# TSOC-ESP8266-EM-1-0.net
KiCad netlist of a schematic drawn in EAGLE
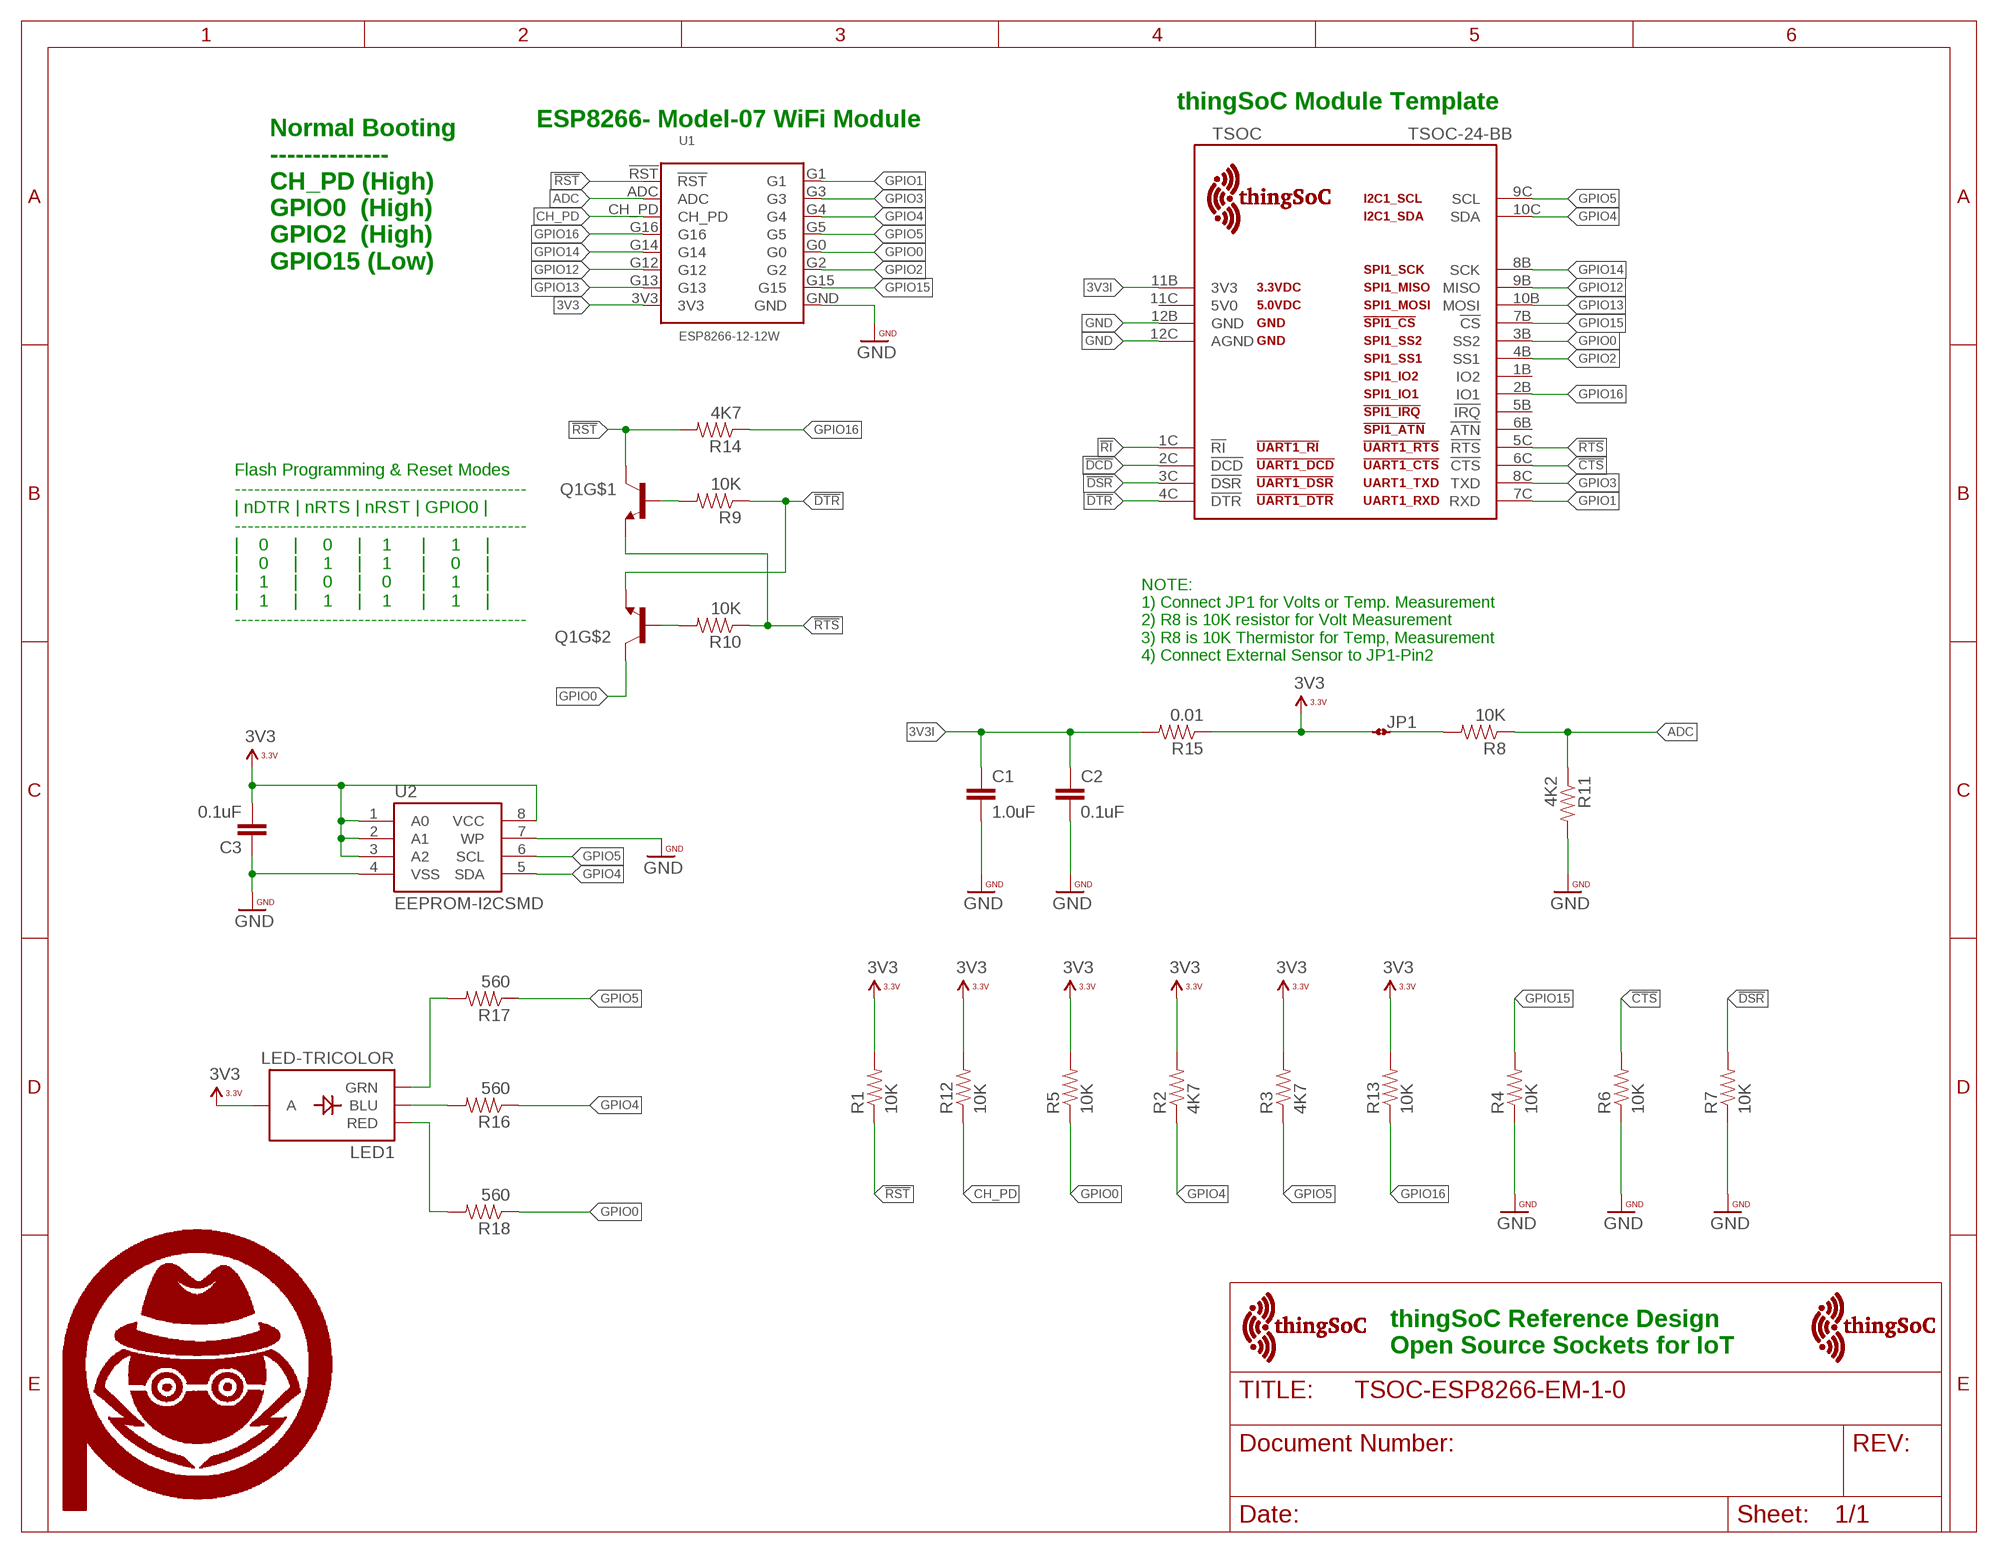
[diagram p0: schematic, sheet 1]

(export (version "E")
  (design (tool "Eeschema 10.0.6"))
  (components
    (comp (ref "C1")
      (value "1.0uF")
      (footprint "eagle-import:0402-CAP")
      (libsource (lib "eagle-import") (part "CAP0402-CAP"))
    )
    (comp (ref "C2")
      (value "0.1uF")
      (footprint "eagle-import:0402-CAP")
      (libsource (lib "eagle-import") (part "CAP0402-CAP"))
    )
    (comp (ref "C3")
      (value "0.1uF")
      (footprint "eagle-import:0402-CAP")
      (libsource (lib "eagle-import") (part "CAP0402-CAP"))
    )
    (comp (ref "JP1")
      (value "JMP-2-NO-0402")
      (footprint "eagle-import:JMP-2-NO-0402")
      (libsource (lib "eagle-import") (part "JMP-2-NO-0402"))
    )
    (comp (ref "LED1")
      (value "LED-TRICOLOR")
      (footprint "eagle-import:LED-TRICOLOR-SMD")
      (libsource (lib "eagle-import") (part "LED-TRICOLOR"))
    )
    (comp (ref "Q1")
      (value "MMBT2222A")
      (footprint "eagle-import:SOT363")
      (libsource (lib "eagle-import") (part "MMDT3904"))
    )
    (comp (ref "R1")
      (value "10K")
      (footprint "eagle-import:0402-RES")
      (libsource (lib "eagle-import") (part "RESISTOR0402"))
    )
    (comp (ref "R2")
      (value "4K7")
      (footprint "eagle-import:0402-RES")
      (libsource (lib "eagle-import") (part "RESISTOR0402"))
    )
    (comp (ref "R3")
      (value "4K7")
      (footprint "eagle-import:0402-RES")
      (libsource (lib "eagle-import") (part "RESISTOR0402"))
    )
    (comp (ref "R4")
      (value "10K")
      (footprint "eagle-import:0402-RES")
      (libsource (lib "eagle-import") (part "RESISTOR0402"))
    )
    (comp (ref "R5")
      (value "10K")
      (footprint "eagle-import:0402-RES")
      (libsource (lib "eagle-import") (part "RESISTOR0402"))
    )
    (comp (ref "R6")
      (value "10K")
      (footprint "eagle-import:0402-RES")
      (libsource (lib "eagle-import") (part "RESISTOR0402"))
    )
    (comp (ref "R7")
      (value "10K")
      (footprint "eagle-import:0402-RES")
      (libsource (lib "eagle-import") (part "RESISTOR0402"))
    )
    (comp (ref "R8")
      (value "10K")
      (footprint "eagle-import:0402-RES")
      (libsource (lib "eagle-import") (part "RESISTOR0402"))
    )
    (comp (ref "R9")
      (value "10K")
      (footprint "eagle-import:0402-RES")
      (libsource (lib "eagle-import") (part "RESISTOR0402"))
    )
    (comp (ref "R10")
      (value "10K")
      (footprint "eagle-import:0402-RES")
      (libsource (lib "eagle-import") (part "RESISTOR0402"))
    )
    (comp (ref "R11")
      (value "4K2")
      (footprint "eagle-import:0402-RES")
      (libsource (lib "eagle-import") (part "RESISTOR0402"))
    )
    (comp (ref "R12")
      (value "10K")
      (footprint "eagle-import:0402-RES")
      (libsource (lib "eagle-import") (part "RESISTOR0402"))
    )
    (comp (ref "R13")
      (value "10K")
      (footprint "eagle-import:0402-RES")
      (libsource (lib "eagle-import") (part "RESISTOR0402"))
    )
    (comp (ref "R14")
      (value "4K7")
      (footprint "eagle-import:0402-RES")
      (libsource (lib "eagle-import") (part "RESISTOR0402"))
    )
    (comp (ref "R15")
      (value "0.01")
      (footprint "eagle-import:0402-RES")
      (libsource (lib "eagle-import") (part "RESISTOR0402"))
    )
    (comp (ref "R16")
      (value "560")
      (footprint "eagle-import:0402-RES")
      (libsource (lib "eagle-import") (part "RESISTOR0402"))
    )
    (comp (ref "R17")
      (value "560")
      (footprint "eagle-import:0402-RES")
      (libsource (lib "eagle-import") (part "RESISTOR0402"))
    )
    (comp (ref "R18")
      (value "560")
      (footprint "eagle-import:0402-RES")
      (libsource (lib "eagle-import") (part "RESISTOR0402"))
    )
    (comp (ref "TSOC")
      (value "TSOC-24-BB")
      (footprint "eagle-import:TSOC-BB-S24")
      (libsource (lib "eagle-import") (part "TSOC-24-BB"))
    )
    (comp (ref "U$11")
      (value "PA_LOGO_SYMMED")
      (footprint "eagle-import:PA_LOGO_AGENT_MED_SYM")
      (libsource (lib "eagle-import") (part "PA_LOGO_SYMMED"))
    )
    (comp (ref "U$19")
      (value "TSOC-LOGO-MED")
      (footprint "eagle-import:TSOC-LOGO-MED")
      (libsource (lib "eagle-import") (part "TSOC-LOGO-MED"))
    )
    (comp (ref "U$20")
      (value "TSOC-LOGO-MED")
      (footprint "eagle-import:TSOC-LOGO-MED")
      (libsource (lib "eagle-import") (part "TSOC-LOGO-MED"))
    )
    (comp (ref "U1")
      (value "ESP8266-12-12W")
      (footprint "eagle-import:ESP8266-12W")
      (libsource (lib "eagle-import") (part "ESP8266-12-12W"))
    )
    (comp (ref "U2")
      (value "EEPROM-I2CSMD")
      (footprint "eagle-import:SO08")
      (libsource (lib "eagle-import") (part "EEPROM-I2CSMD"))
    )
  )
  (nets
    (net (code "1") (name "/~{CTS}") (class "Default")
      (node (ref "R6") (pin "2") (pinfunction "2_2") (pintype "passive"))
      (node (ref "TSOC") (pin "6C") (pinfunction "~{CTS}_6C") (pintype "bidirectional"))
    )
    (net (code "2") (name "/~{DCD}") (class "Default")
      (node (ref "TSOC") (pin "2C") (pinfunction "~{DCD}_2C") (pintype "bidirectional"))
    )
    (net (code "3") (name "/~{DSR}") (class "Default")
      (node (ref "R7") (pin "2") (pinfunction "2_2") (pintype "passive"))
      (node (ref "TSOC") (pin "3C") (pinfunction "~{DSR}_3C") (pintype "bidirectional"))
    )
    (net (code "4") (name "/~{DTR}") (class "Default")
      (node (ref "Q1") (pin "1") (pinfunction "E_1") (pintype "passive"))
      (node (ref "R9") (pin "1") (pinfunction "1_1") (pintype "passive"))
      (node (ref "TSOC") (pin "4C") (pinfunction "~{DTR}_4C") (pintype "bidirectional"))
    )
    (net (code "5") (name "/~{RI}") (class "Default")
      (node (ref "TSOC") (pin "1C") (pinfunction "~{RI}_1C") (pintype "bidirectional"))
    )
    (net (code "6") (name "/~{RST}") (class "Default")
      (node (ref "Q1") (pin "3") (pinfunction "C_3") (pintype "passive"))
      (node (ref "R1") (pin "1") (pinfunction "1_1") (pintype "passive"))
      (node (ref "R14") (pin "2") (pinfunction "2_2") (pintype "passive"))
      (node (ref "U1") (pin "!RST") (pinfunction "~{RST}_!RST") (pintype "bidirectional"))
    )
    (net (code "7") (name "/~{RTS}") (class "Default")
      (node (ref "Q1") (pin "4") (pinfunction "E_4") (pintype "passive"))
      (node (ref "R10") (pin "1") (pinfunction "1_1") (pintype "passive"))
      (node (ref "TSOC") (pin "5C") (pinfunction "~{RTS}_5C") (pintype "bidirectional"))
    )
    (net (code "8") (name "3V3") (class "Default")
      (node (ref "C3") (pin "2") (pinfunction "2_2") (pintype "passive"))
      (node (ref "JP1") (pin "1") (pinfunction "1_1") (pintype "passive"))
      (node (ref "LED1") (pin "A") (pinfunction "A_A") (pintype "bidirectional"))
      (node (ref "R1") (pin "2") (pinfunction "2_2") (pintype "passive"))
      (node (ref "R12") (pin "2") (pinfunction "2_2") (pintype "passive"))
      (node (ref "R13") (pin "2") (pinfunction "2_2") (pintype "passive"))
      (node (ref "R15") (pin "1") (pinfunction "1_1") (pintype "passive"))
      (node (ref "R2") (pin "2") (pinfunction "2_2") (pintype "passive"))
      (node (ref "R3") (pin "2") (pinfunction "2_2") (pintype "passive"))
      (node (ref "R5") (pin "2") (pinfunction "2_2") (pintype "passive"))
      (node (ref "U1") (pin "3V3") (pinfunction "3V3_3V3") (pintype "bidirectional"))
      (node (ref "U2") (pin "1") (pinfunction "A0_1") (pintype "bidirectional"))
      (node (ref "U2") (pin "2") (pinfunction "A1_2") (pintype "bidirectional"))
      (node (ref "U2") (pin "3") (pinfunction "A2_3") (pintype "bidirectional"))
      (node (ref "U2") (pin "8") (pinfunction "VCC_8") (pintype "power_in"))
    )
    (net (code "9") (name "3V3I") (class "Default")
      (node (ref "C1") (pin "1") (pinfunction "1_1") (pintype "passive"))
      (node (ref "C2") (pin "1") (pinfunction "1_1") (pintype "passive"))
      (node (ref "R15") (pin "2") (pinfunction "2_2") (pintype "passive"))
      (node (ref "TSOC") (pin "11B") (pinfunction "3V3_11B") (pintype "bidirectional"))
    )
    (net (code "10") (name "ADC") (class "Default")
      (node (ref "R11") (pin "1") (pinfunction "1_1") (pintype "passive"))
      (node (ref "R8") (pin "1") (pinfunction "1_1") (pintype "passive"))
      (node (ref "U1") (pin "ADC") (pinfunction "ADC_ADC") (pintype "bidirectional"))
    )
    (net (code "11") (name "CH_PD") (class "Default")
      (node (ref "R12") (pin "1") (pinfunction "1_1") (pintype "passive"))
      (node (ref "U1") (pin "CH_PD") (pinfunction "CH_PD_CH_PD") (pintype "bidirectional"))
    )
    (net (code "12") (name "GND") (class "Default")
      (node (ref "C1") (pin "2") (pinfunction "2_2") (pintype "passive"))
      (node (ref "C2") (pin "2") (pinfunction "2_2") (pintype "passive"))
      (node (ref "C3") (pin "1") (pinfunction "1_1") (pintype "passive"))
      (node (ref "R11") (pin "2") (pinfunction "2_2") (pintype "passive"))
      (node (ref "R4") (pin "1") (pinfunction "1_1") (pintype "passive"))
      (node (ref "R6") (pin "1") (pinfunction "1_1") (pintype "passive"))
      (node (ref "R7") (pin "1") (pinfunction "1_1") (pintype "passive"))
      (node (ref "TSOC") (pin "12B") (pinfunction "GND_12B") (pintype "bidirectional"))
      (node (ref "TSOC") (pin "12C") (pinfunction "AGND_12C") (pintype "bidirectional"))
      (node (ref "U1") (pin "GND") (pinfunction "GND_GND") (pintype "bidirectional"))
      (node (ref "U2") (pin "4") (pinfunction "VSS_4") (pintype "power_in"))
      (node (ref "U2") (pin "7") (pinfunction "WP_7") (pintype "bidirectional"))
    )
    (net (code "13") (name "GPIO0") (class "Default")
      (node (ref "Q1") (pin "6") (pinfunction "C_6") (pintype "passive"))
      (node (ref "R18") (pin "1") (pinfunction "1_1") (pintype "passive"))
      (node (ref "R5") (pin "1") (pinfunction "1_1") (pintype "passive"))
      (node (ref "TSOC") (pin "3B") (pinfunction "SS2_3B") (pintype "bidirectional"))
      (node (ref "U1") (pin "G0") (pinfunction "G0_G0") (pintype "bidirectional"))
    )
    (net (code "14") (name "GPIO1") (class "Default")
      (node (ref "TSOC") (pin "7C") (pinfunction "RXD_7C") (pintype "bidirectional"))
      (node (ref "U1") (pin "G1") (pinfunction "G1_G1") (pintype "bidirectional"))
    )
    (net (code "15") (name "GPIO2") (class "Default")
      (node (ref "TSOC") (pin "4B") (pinfunction "SS1_4B") (pintype "bidirectional"))
      (node (ref "U1") (pin "G2") (pinfunction "G2_G2") (pintype "bidirectional"))
    )
    (net (code "16") (name "GPIO3") (class "Default")
      (node (ref "TSOC") (pin "8C") (pinfunction "TXD_8C") (pintype "bidirectional"))
      (node (ref "U1") (pin "G3") (pinfunction "G3_G3") (pintype "bidirectional"))
    )
    (net (code "17") (name "GPIO4") (class "Default")
      (node (ref "R16") (pin "1") (pinfunction "1_1") (pintype "passive"))
      (node (ref "R2") (pin "1") (pinfunction "1_1") (pintype "passive"))
      (node (ref "TSOC") (pin "10C") (pinfunction "SDA_10C") (pintype "bidirectional"))
      (node (ref "U1") (pin "G4") (pinfunction "G4_G4") (pintype "bidirectional"))
      (node (ref "U2") (pin "5") (pinfunction "SDA_5") (pintype "bidirectional"))
    )
    (net (code "18") (name "GPIO5") (class "Default")
      (node (ref "R17") (pin "1") (pinfunction "1_1") (pintype "passive"))
      (node (ref "R3") (pin "1") (pinfunction "1_1") (pintype "passive"))
      (node (ref "TSOC") (pin "9C") (pinfunction "SCL_9C") (pintype "bidirectional"))
      (node (ref "U1") (pin "G5") (pinfunction "G5_G5") (pintype "bidirectional"))
      (node (ref "U2") (pin "6") (pinfunction "SCL_6") (pintype "bidirectional"))
    )
    (net (code "19") (name "GPIO12") (class "Default")
      (node (ref "TSOC") (pin "9B") (pinfunction "MISO_9B") (pintype "bidirectional"))
      (node (ref "U1") (pin "G12") (pinfunction "G12_G12") (pintype "bidirectional"))
    )
    (net (code "20") (name "GPIO13") (class "Default")
      (node (ref "TSOC") (pin "10B") (pinfunction "MOSI_10B") (pintype "bidirectional"))
      (node (ref "U1") (pin "G13") (pinfunction "G13_G13") (pintype "bidirectional"))
    )
    (net (code "21") (name "GPIO14") (class "Default")
      (node (ref "TSOC") (pin "8B") (pinfunction "SCK_8B") (pintype "bidirectional"))
      (node (ref "U1") (pin "G14") (pinfunction "G14_G14") (pintype "bidirectional"))
    )
    (net (code "22") (name "GPIO15") (class "Default")
      (node (ref "R4") (pin "2") (pinfunction "2_2") (pintype "passive"))
      (node (ref "TSOC") (pin "7B") (pinfunction "~{CS}_7B") (pintype "bidirectional"))
      (node (ref "U1") (pin "G15") (pinfunction "G15_G15") (pintype "bidirectional"))
    )
    (net (code "23") (name "GPIO16") (class "Default")
      (node (ref "R13") (pin "1") (pinfunction "1_1") (pintype "passive"))
      (node (ref "R14") (pin "1") (pinfunction "1_1") (pintype "passive"))
      (node (ref "TSOC") (pin "2B") (pinfunction "IO1_2B") (pintype "bidirectional"))
      (node (ref "U1") (pin "G16") (pinfunction "G16_G16") (pintype "bidirectional"))
    )
    (net (code "24") (name "Net-(JP1-Pad2)") (class "Default")
      (node (ref "JP1") (pin "2") (pinfunction "2_2") (pintype "passive"))
      (node (ref "R8") (pin "2") (pinfunction "2_2") (pintype "passive"))
    )
    (net (code "25") (name "Net-(LED1-BLU)") (class "Default")
      (node (ref "LED1") (pin "B") (pinfunction "BLU_B") (pintype "bidirectional"))
      (node (ref "R16") (pin "2") (pinfunction "2_2") (pintype "passive"))
    )
    (net (code "26") (name "Net-(LED1-GRN)") (class "Default")
      (node (ref "LED1") (pin "G") (pinfunction "GRN_G") (pintype "bidirectional"))
      (node (ref "R17") (pin "2") (pinfunction "2_2") (pintype "passive"))
    )
    (net (code "27") (name "Net-(LED1-RED)") (class "Default")
      (node (ref "LED1") (pin "R") (pinfunction "RED_R") (pintype "bidirectional"))
      (node (ref "R18") (pin "2") (pinfunction "2_2") (pintype "passive"))
    )
    (net (code "28") (name "Net-(Q1A-B)") (class "Default")
      (node (ref "Q1") (pin "5") (pinfunction "B_5") (pintype "passive"))
      (node (ref "R9") (pin "2") (pinfunction "2_2") (pintype "passive"))
    )
    (net (code "29") (name "Net-(Q1B-B)") (class "Default")
      (node (ref "Q1") (pin "2") (pinfunction "B_2") (pintype "passive"))
      (node (ref "R10") (pin "2") (pinfunction "2_2") (pintype "passive"))
    )
    (net (code "30") (name "unconnected-(TSOC-5V0-Pad11C)") (class "Default")
      (node (ref "TSOC") (pin "11C") (pinfunction "5V0_11C") (pintype "bidirectional"))
    )
    (net (code "31") (name "unconnected-(TSOC-IO2-Pad1B)") (class "Default")
      (node (ref "TSOC") (pin "1B") (pinfunction "IO2_1B") (pintype "bidirectional"))
    )
    (net (code "32") (name "unconnected-(TSOC-~{ATN}-Pad6B)") (class "Default")
      (node (ref "TSOC") (pin "6B") (pinfunction "~{ATN}_6B") (pintype "bidirectional"))
    )
    (net (code "33") (name "unconnected-(TSOC-~{IRQ}-Pad5B)") (class "Default")
      (node (ref "TSOC") (pin "5B") (pinfunction "~{IRQ}_5B") (pintype "bidirectional"))
    )
  )
)
